# PCAL64.net
KiCad netlist of a schematic drawn in Altium Designer
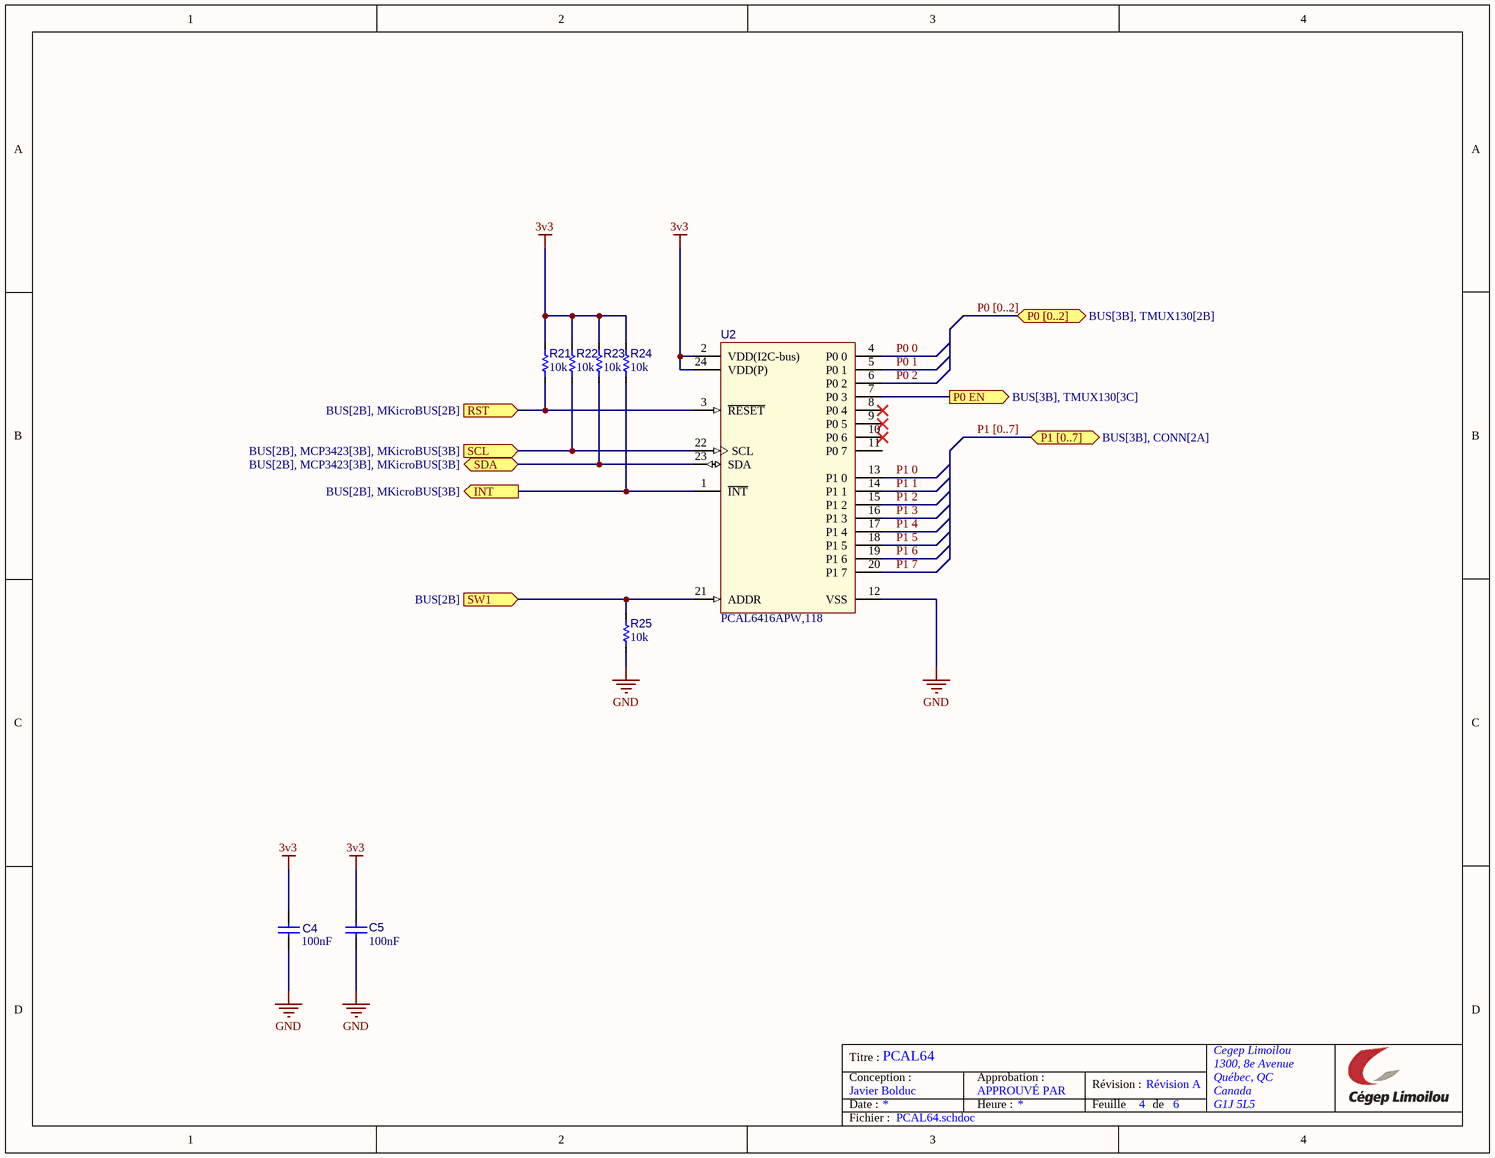
[diagram p0: PCAL64.schdoc]

(export (version "E")
  (design (tool "Eeschema 10.0.6"))
  (components
    (comp (ref "C4")
      (value "100nF")
      (footprint "C_1608[0603]")
      (description "Capacitor type 1")
      (fields (field (name "TOLERANCE") "10%") (field (name "Comment") "CAP CER 100nF 50V 0603"))
      (libsource (lib "TEP-AltiumLib-Passives-RLC") (part "capacitor"))
    )
    (comp (ref "C5")
      (value "100nF")
      (footprint "C_1608[0603]")
      (description "Capacitor type 1")
      (fields (field (name "TOLERANCE") "10%") (field (name "Comment") "CAP CER 100nF 50V 0603"))
      (libsource (lib "TEP-AltiumLib-Passives-RLC") (part "capacitor"))
    )
    (comp (ref "R21")
      (value "10k")
      (footprint "R_1608[0603]")
      (description "Resistor type 1")
      (fields (field (name "TOLERANCE") "1%") (field (name "Comment") "Res 10k 1% 0603"))
      (libsource (lib "TEP-AltiumLib-Passives-RLC") (part "resistor"))
    )
    (comp (ref "R22")
      (value "10k")
      (footprint "R_1608[0603]")
      (description "Resistor type 1")
      (fields (field (name "TOLERANCE") "1%") (field (name "Comment") "Res 10k 1% 0603"))
      (libsource (lib "TEP-AltiumLib-Passives-RLC") (part "resistor"))
    )
    (comp (ref "R23")
      (value "10k")
      (footprint "R_1608[0603]")
      (description "Resistor type 1")
      (fields (field (name "TOLERANCE") "1%") (field (name "Comment") "Res 10k 1% 0603"))
      (libsource (lib "TEP-AltiumLib-Passives-RLC") (part "resistor"))
    )
    (comp (ref "R24")
      (value "10k")
      (footprint "R_1608[0603]")
      (description "Resistor type 1")
      (fields (field (name "TOLERANCE") "1%") (field (name "Comment") "Res 10k 1% 0603"))
      (libsource (lib "TEP-AltiumLib-Passives-RLC") (part "resistor"))
    )
    (comp (ref "R25")
      (value "10k")
      (footprint "R_1608[0603]")
      (description "Resistor type 1")
      (fields (field (name "TOLERANCE") "1%") (field (name "Comment") "Res 10k 1% 0603"))
      (libsource (lib "TEP-AltiumLib-Passives-RLC") (part "resistor"))
    )
    (comp (ref "U2")
      (value "PCAL6416APW,118")
      (footprint "U_TSSOP24_SOT355-1-IPC_B")
      (description "IC I/O EXPANDER 16BIT 24TSSOP")
      (libsource (lib "TEP-AltiumLib-ICs") (part "U_PCAL6416APW"))
    )
  )
  (nets
    (net (code "1") (name "/INT") (class "Default")
      (node (ref "R24") (pin "2") (pinfunction "2_2") (pintype "passive"))
      (node (ref "U2") (pin "1") (pinfunction "~{INT}_1") (pintype "open_collector"))
    )
    (net (code "2") (name "/P0 0") (class "Default")
      (node (ref "U2") (pin "4") (pinfunction "P0_0_4") (pintype "passive"))
    )
    (net (code "3") (name "/P0 1") (class "Default")
      (node (ref "U2") (pin "5") (pinfunction "P0_1_5") (pintype "passive"))
    )
    (net (code "4") (name "/P0 2") (class "Default")
      (node (ref "U2") (pin "6") (pinfunction "P0_2_6") (pintype "passive"))
    )
    (net (code "5") (name "/P0 EN") (class "Default")
      (node (ref "U2") (pin "7") (pinfunction "P0_3_7") (pintype "passive"))
    )
    (net (code "6") (name "/P1 0") (class "Default")
      (node (ref "U2") (pin "13") (pinfunction "P1_0_13") (pintype "passive"))
    )
    (net (code "7") (name "/P1 1") (class "Default")
      (node (ref "U2") (pin "14") (pinfunction "P1_1_14") (pintype "passive"))
    )
    (net (code "8") (name "/P1 2") (class "Default")
      (node (ref "U2") (pin "15") (pinfunction "P1_2_15") (pintype "passive"))
    )
    (net (code "9") (name "/P1 3") (class "Default")
      (node (ref "U2") (pin "16") (pinfunction "P1_3_16") (pintype "passive"))
    )
    (net (code "10") (name "/P1 4") (class "Default")
      (node (ref "U2") (pin "17") (pinfunction "P1_4_17") (pintype "passive"))
    )
    (net (code "11") (name "/P1 5") (class "Default")
      (node (ref "U2") (pin "18") (pinfunction "P1_5_18") (pintype "passive"))
    )
    (net (code "12") (name "/P1 6") (class "Default")
      (node (ref "U2") (pin "19") (pinfunction "P1_6_19") (pintype "passive"))
    )
    (net (code "13") (name "/P1 7") (class "Default")
      (node (ref "U2") (pin "20") (pinfunction "P1_7_20") (pintype "passive"))
    )
    (net (code "14") (name "/RST") (class "Default")
      (node (ref "R21") (pin "2") (pinfunction "2_2") (pintype "passive"))
      (node (ref "U2") (pin "3") (pinfunction "~{RESET}_3") (pintype "input"))
    )
    (net (code "15") (name "/SCL") (class "Default")
      (node (ref "R22") (pin "2") (pinfunction "2_2") (pintype "passive"))
      (node (ref "U2") (pin "22") (pinfunction "SCL_22") (pintype "input"))
    )
    (net (code "16") (name "/SDA") (class "Default")
      (node (ref "R23") (pin "2") (pinfunction "2_2") (pintype "passive"))
      (node (ref "U2") (pin "23") (pinfunction "SDA_23") (pintype "bidirectional"))
    )
    (net (code "17") (name "/SW1") (class "Default")
      (node (ref "R25") (pin "1") (pinfunction "1_1") (pintype "passive"))
      (node (ref "U2") (pin "21") (pinfunction "ADDR_21") (pintype "input"))
    )
    (net (code "20") (name "3v3") (class "Default")
      (node (ref "C4") (pin "2") (pinfunction "2_2") (pintype "passive"))
      (node (ref "C5") (pin "2") (pinfunction "2_2") (pintype "passive"))
      (node (ref "R21") (pin "1") (pinfunction "1_1") (pintype "passive"))
      (node (ref "R22") (pin "1") (pinfunction "1_1") (pintype "passive"))
      (node (ref "R23") (pin "1") (pinfunction "1_1") (pintype "passive"))
      (node (ref "R24") (pin "1") (pinfunction "1_1") (pintype "passive"))
      (node (ref "U2") (pin "2") (pinfunction "VDD(I2C-bus)_2") (pintype "power_in"))
      (node (ref "U2") (pin "24") (pinfunction "VDD(P)_24") (pintype "power_in"))
    )
    (net (code "21") (name "GND") (class "Default")
      (node (ref "C4") (pin "1") (pinfunction "1_1") (pintype "passive"))
      (node (ref "C5") (pin "1") (pinfunction "1_1") (pintype "passive"))
      (node (ref "R25") (pin "2") (pinfunction "2_2") (pintype "passive"))
      (node (ref "U2") (pin "12") (pinfunction "VSS_12") (pintype "power_in"))
    )
    (net (code "22") (name "unconnected-(U2-P0_4-Pad8)") (class "Default")
      (node (ref "U2") (pin "8") (pinfunction "P0_4_8") (pintype "passive+no_connect"))
    )
    (net (code "23") (name "unconnected-(U2-P0_5-Pad9)") (class "Default")
      (node (ref "U2") (pin "9") (pinfunction "P0_5_9") (pintype "passive+no_connect"))
    )
    (net (code "24") (name "unconnected-(U2-P0_6-Pad10)") (class "Default")
      (node (ref "U2") (pin "10") (pinfunction "P0_6_10") (pintype "passive+no_connect"))
    )
    (net (code "25") (name "unconnected-(U2-P0_7-Pad11)") (class "Default")
      (node (ref "U2") (pin "11") (pinfunction "P0_7_11") (pintype "passive"))
    )
  )
)
